# independent_5V.net
KiCad netlist of a schematic drawn in Altium Designer
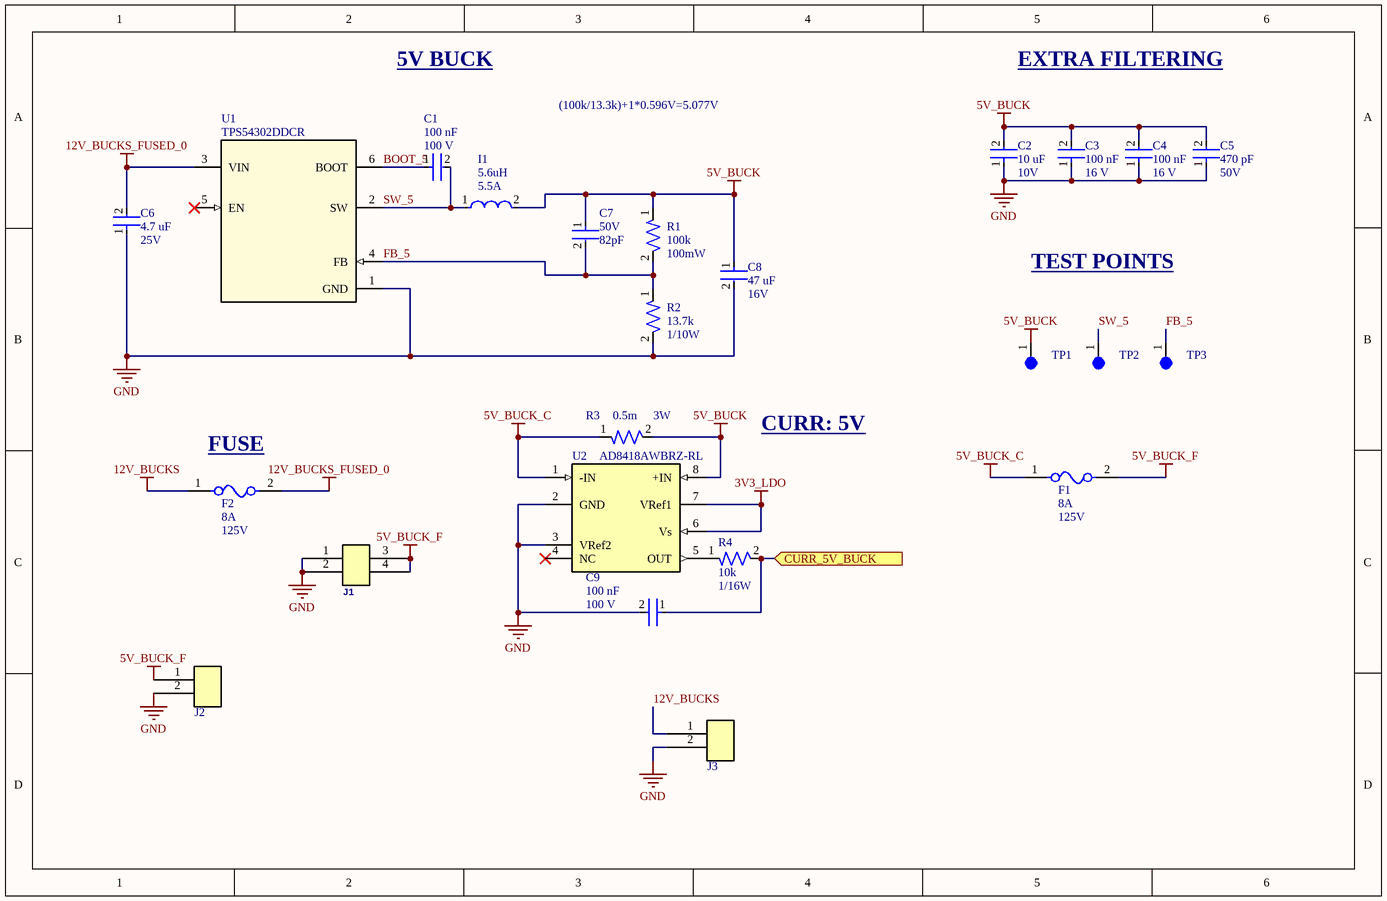
[diagram p0: independent_5V.SchDoc]

(export (version "E")
  (design (tool "Eeschema 10.0.6"))
  (components
    (comp (ref "C1")
      (value "CC0603KRX7R0BB104")
      (footprint "CAP-0603")
      (description "CAP CER 0.1UF 100V X7R 0603")
      (fields (field (name "CAPACITANCE") "100 nF") (field (name "VOLTAGE") "100 V"))
      (libsource (lib "JLC_25") (part "CAP-100N-0001"))
    )
    (comp (ref "C2")
      (value "CC0603KRX5R6BB106")
      (footprint "CAP-0603")
      (description "CAP CER 10UF 10V X5R 0603")
      (fields (field (name "VOLTAGE") "10V") (field (name "CAPACITANCE") "10 uF"))
      (libsource (lib "JLC_25") (part "CAP-10U-0001"))
    )
    (comp (ref "C3")
      (value "CC0402KRX7R7BB104")
      (footprint "CAP-0402")
      (description "CAP CER 0.1UF 16V X7R 0402")
      (fields (field (name "VOLTAGE RATING") "16 V") (field (name "CAPACITANCE") "100 nF"))
      (libsource (lib "JLC_25") (part "CAP-0.1U-0001"))
    )
    (comp (ref "C4")
      (value "CC0402KRX7R7BB104")
      (footprint "CAP-0402")
      (description "CAP CER 0.1UF 16V X7R 0402")
      (fields (field (name "VOLTAGE RATING") "16 V") (field (name "CAPACITANCE") "100 nF"))
      (libsource (lib "JLC_25") (part "CAP-0.1U-0001"))
    )
    (comp (ref "C5")
      (value "CC0805JRNPO9BN471")
      (footprint "CAP-0805")
      (description "CAP CER 470PF 50V C0G/NPO 0805")
      (fields (field (name "VOLTAGE") "50V") (field (name "CAPACITANCE") "470 pF"))
      (libsource (lib "JLC_25") (part "CAP-470P-0001"))
    )
    (comp (ref "C6")
      (value "CC0603KRX5R8BB475")
      (footprint "CAP-0603")
      (description "CAP CER 4.7UF 25V X5R 0603")
      (fields (field (name "CAPACITANCE") "4.7 uF") (field (name "VOLTAGE") "25V"))
      (libsource (lib "JLC_25") (part "CAP-4.7U-0001"))
    )
    (comp (ref "C7")
      (value "CC0805JRNPO9BN820")
      (footprint "CAP-0805")
      (description "82 pF ±5% 50V Ceramic Capacitor C0G, NP0 0805 (2012 Metric)")
      (fields (field (name "VOLTAGE") "50V") (field (name "CAPACITANCE") "82pF"))
      (libsource (lib "JLC_25") (part "CAP-82P-0001"))
    )
    (comp (ref "C8")
      (value "GRM32ER61C476KE15L")
      (footprint "CAP-1210")
      (description "CAP CER 47UF 16V X5R 1210")
      (fields (field (name "CAPACITANCE") "47 uF") (field (name "VOLTAGE") "16V"))
      (libsource (lib "JLC_25") (part "CAP-47U-0002"))
    )
    (comp (ref "C9")
      (value "CC0603KRX7R0BB104")
      (footprint "CAP-0603")
      (description "CAP CER 0.1UF 100V X7R 0603")
      (fields (field (name "CAPACITANCE") "100 nF") (field (name "VOLTAGE") "100 V"))
      (libsource (lib "JLC_25") (part "CAP-100N-0001"))
    )
    (comp (ref "F1")
      (value "01550900M")
      (footprint "FUSE-0001")
      (description "FUSE BLOK CARTRIDGE 125V 10A SMD")
      (fields (field (name "FUSE CURRENT") "8A") (field (name "VOLTAGE RATING") "125V"))
      (libsource (lib "JLC_25") (part "FUSE-0001"))
    )
    (comp (ref "F2")
      (value "01550900M")
      (footprint "FUSE-0001")
      (description "FUSE BLOK CARTRIDGE 125V 10A SMD")
      (fields (field (name "FUSE CURRENT") "8A") (field (name "VOLTAGE RATING") "125V"))
      (libsource (lib "JLC_25") (part "FUSE-0001"))
    )
    (comp (ref "I1")
      (value "SRP6540-5R6M")
      (footprint "IND_SRP6540-5R6M")
      (description "FIXED IND 5.6UH 5.5A 38 MOHM SMD")
      (fields (field (name "SATURATION CURRENT") "5.5A") (field (name "INDUCTANCE") "5.6uH"))
      (libsource (lib "JLC_25") (part "IND-5.6U-0002"))
    )
    (comp (ref "J1")
      (value "Molex 43045-0412")
      (footprint "CONN-4POS-0002")
      (description "CONN HEADER VERT 4POS 3MM")
      (libsource (lib "JLC_25") (part "CONN-4POS-0002"))
    )
    (comp (ref "J2")
      (value "0436500215")
      (footprint "CONN-2POS-0002")
      (description "CONN HEADER VERT 2POS 3MM")
      (libsource (lib "JLC_25") (part "CONN-2POS-0002"))
    )
    (comp (ref "J3")
      (value "0430450212")
      (footprint "CONN-2POS-0001")
      (description "CONN HEADER VERT 2POS")
      (libsource (lib "JLC_25") (part "CONN-2POS-0001"))
    )
    (comp (ref "R1")
      (value "RC0603FR-07100KL")
      (footprint "RES-0603")
      (description "RES SMD 100K OHM 1% 1/10W 0603")
      (fields
        (field (name "TOLERANCE") "1%")
        (field (name "POWER") "100mW")
        (field (name "RESISTANCE") "100k")
      )
      (libsource (lib "JLC_25") (part "RES-100k-0001"))
    )
    (comp (ref "R2")
      (value "RC0603FR-0713K7L")
      (footprint "RES-0603")
      (description "RES 13.7K OHM 1% 1/10W 0603")
      (fields (field (name "POWER") "1/10W") (field (name "RESISTANCE") "13.7k"))
      (libsource (lib "JLC_25") (part "RES-13.7K-0001"))
    )
    (comp (ref "R3")
      (value "CSNL2512FTL500")
      (footprint "RES-2512")
      (description "2512 Chip Resistor - Surface Mount ROHS")
      (fields (field (name "TOLERANCE") "1%") (field (name "POWER") "3W") (field (name "RESISTANCE") "0.5m"))
      (libsource (lib "JLC_25") (part "RES-0.5m-0001"))
    )
    (comp (ref "R4")
      (value "RC0402FR-0710KL")
      (footprint "RES-0402")
      (description "RES 10K OHM 1% 1/16W 0402")
      (fields
        (field (name "TOLERANCE") "1%")
        (field (name "RESISTANCE") "10k")
        (field (name "POWER") "1/16W")
      )
      (libsource (lib "JLC_25") (part "RES-10k-0001"))
    )
    (comp (ref "TP1")
      (value "5003")
      (footprint "TEST-POINT-0001")
      (description "Oranange PC Test Point, Miniature Phoisphor Bronze Silver Plating Through Hole Mounting Type")
      (libsource (lib "*") (part "TEST-POINT-0001"))
    )
    (comp (ref "TP2")
      (value "5003")
      (footprint "TEST-POINT-0001")
      (description "Oranange PC Test Point, Miniature Phoisphor Bronze Silver Plating Through Hole Mounting Type")
      (libsource (lib "*") (part "TEST-POINT-0001"))
    )
    (comp (ref "TP3")
      (value "5003")
      (footprint "TEST-POINT-0001")
      (description "Oranange PC Test Point, Miniature Phoisphor Bronze Silver Plating Through Hole Mounting Type")
      (libsource (lib "*") (part "TEST-POINT-0001"))
    )
    (comp (ref "U1")
      (value "TPS54302DDCR")
      (footprint "IC-SOT-23-6")
      (description "IC REG BUCK ADJ 3A SOT23")
      (libsource (lib "JLC_25") (part "IC-BUCK-0004"))
    )
    (comp (ref "U2")
      (value "AD8418AWBRZ-RL")
      (footprint "IC-CURR")
      (description "Current Sense Amplifier 1 Circuit 8-MSOP")
      (libsource (lib "JLC_25") (part "IC-CURR-0001"))
    )
  )
  (nets
    (net (code "1") (name "/BOOT_5") (class "Default")
      (node (ref "C1") (pin "1") (pinfunction "1_1") (pintype "passive"))
      (node (ref "U1") (pin "6") (pinfunction "BOOT_6") (pintype "power_in"))
    )
    (net (code "2") (name "/CURR_5V_BUCK") (class "Default")
      (node (ref "C9") (pin "1") (pinfunction "1_1") (pintype "passive"))
      (node (ref "R4") (pin "2") (pinfunction "2_2") (pintype "passive"))
    )
    (net (code "3") (name "/FB_5") (class "Default")
      (node (ref "C7") (pin "2") (pinfunction "2_2") (pintype "passive"))
      (node (ref "R1") (pin "2") (pinfunction "2_2") (pintype "passive"))
      (node (ref "R2") (pin "1") (pinfunction "1_1") (pintype "passive"))
      (node (ref "TP3") (pin "1") (pinfunction "0_1") (pintype "passive"))
      (node (ref "U1") (pin "4") (pinfunction "FB_4") (pintype "input"))
    )
    (net (code "4") (name "/SW_5") (class "Default")
      (node (ref "C1") (pin "2") (pinfunction "2_2") (pintype "passive"))
      (node (ref "I1") (pin "1") (pinfunction "1_1") (pintype "passive"))
      (node (ref "TP2") (pin "1") (pinfunction "0_1") (pintype "passive"))
      (node (ref "U1") (pin "2") (pinfunction "SW_2") (pintype "power_in"))
    )
    (net (code "5") (name "3V3_LDO") (class "Default")
      (node (ref "U2") (pin "6") (pinfunction "Vs_6") (pintype "input"))
      (node (ref "U2") (pin "7") (pinfunction "VRef1_7") (pintype "power_in"))
    )
    (net (code "6") (name "5V_BUCK") (class "Default")
      (node (ref "C2") (pin "2") (pinfunction "2_2") (pintype "passive"))
      (node (ref "C3") (pin "2") (pinfunction "2_2") (pintype "passive"))
      (node (ref "C4") (pin "2") (pinfunction "2_2") (pintype "passive"))
      (node (ref "C5") (pin "2") (pinfunction "2_2") (pintype "passive"))
      (node (ref "C7") (pin "1") (pinfunction "1_1") (pintype "passive"))
      (node (ref "C8") (pin "1") (pinfunction "1_1") (pintype "passive"))
      (node (ref "I1") (pin "2") (pinfunction "2_2") (pintype "passive"))
      (node (ref "R1") (pin "1") (pinfunction "1_1") (pintype "passive"))
      (node (ref "R3") (pin "2") (pinfunction "2_2") (pintype "passive"))
      (node (ref "TP1") (pin "1") (pinfunction "0_1") (pintype "passive"))
      (node (ref "U2") (pin "8") (pinfunction "+IN_8") (pintype "input"))
    )
    (net (code "7") (name "5V_BUCK_C") (class "Default")
      (node (ref "F1") (pin "1") (pinfunction "1_1") (pintype "passive"))
      (node (ref "R3") (pin "1") (pinfunction "1_1") (pintype "passive"))
      (node (ref "U2") (pin "1") (pinfunction "-IN_1") (pintype "input"))
    )
    (net (code "8") (name "5V_BUCK_F") (class "Default")
      (node (ref "F1") (pin "2") (pinfunction "2_2") (pintype "passive"))
      (node (ref "J1") (pin "3") (pinfunction "3_3") (pintype "passive"))
      (node (ref "J1") (pin "4") (pinfunction "4_4") (pintype "passive"))
      (node (ref "J2") (pin "1") (pinfunction "7_1") (pintype "passive"))
    )
    (net (code "9") (name "12V_BUCKS") (class "Default")
      (node (ref "F2") (pin "1") (pinfunction "1_1") (pintype "passive"))
      (node (ref "J3") (pin "1") (pinfunction "7_1") (pintype "passive"))
    )
    (net (code "10") (name "12V_BUCKS_FUSED_0") (class "Default")
      (node (ref "C6") (pin "2") (pinfunction "2_2") (pintype "passive"))
      (node (ref "F2") (pin "2") (pinfunction "2_2") (pintype "passive"))
      (node (ref "U1") (pin "3") (pinfunction "VIN_3") (pintype "power_in"))
    )
    (net (code "11") (name "GND") (class "Default")
      (node (ref "C2") (pin "1") (pinfunction "1_1") (pintype "passive"))
      (node (ref "C3") (pin "1") (pinfunction "1_1") (pintype "passive"))
      (node (ref "C4") (pin "1") (pinfunction "1_1") (pintype "passive"))
      (node (ref "C5") (pin "1") (pinfunction "1_1") (pintype "passive"))
      (node (ref "C6") (pin "1") (pinfunction "1_1") (pintype "passive"))
      (node (ref "C8") (pin "2") (pinfunction "2_2") (pintype "passive"))
      (node (ref "C9") (pin "2") (pinfunction "2_2") (pintype "passive"))
      (node (ref "J1") (pin "1") (pinfunction "1_1") (pintype "passive"))
      (node (ref "J1") (pin "2") (pinfunction "2_2") (pintype "passive"))
      (node (ref "J2") (pin "2") (pinfunction "8_2") (pintype "passive"))
      (node (ref "J3") (pin "2") (pinfunction "8_2") (pintype "passive"))
      (node (ref "R2") (pin "2") (pinfunction "2_2") (pintype "passive"))
      (node (ref "U1") (pin "1") (pinfunction "GND_1") (pintype "power_in"))
      (node (ref "U2") (pin "2") (pinfunction "GND_2") (pintype "power_in"))
      (node (ref "U2") (pin "3") (pinfunction "VRef2_3") (pintype "passive"))
    )
    (net (code "12") (name "Net-(U2-OUT)") (class "Default")
      (node (ref "R4") (pin "1") (pinfunction "1_1") (pintype "passive"))
      (node (ref "U2") (pin "5") (pinfunction "OUT_5") (pintype "output"))
    )
    (net (code "13") (name "unconnected-(U1-EN-Pad5)") (class "Default")
      (node (ref "U1") (pin "5") (pinfunction "EN_5") (pintype "input+no_connect"))
    )
    (net (code "14") (name "unconnected-(U2-NC-Pad4)") (class "Default")
      (node (ref "U2") (pin "4") (pinfunction "NC_4") (pintype "passive+no_connect"))
    )
  )
)
